# ARDEC-controller-v1.net
KiCad netlist of a schematic drawn in EAGLE
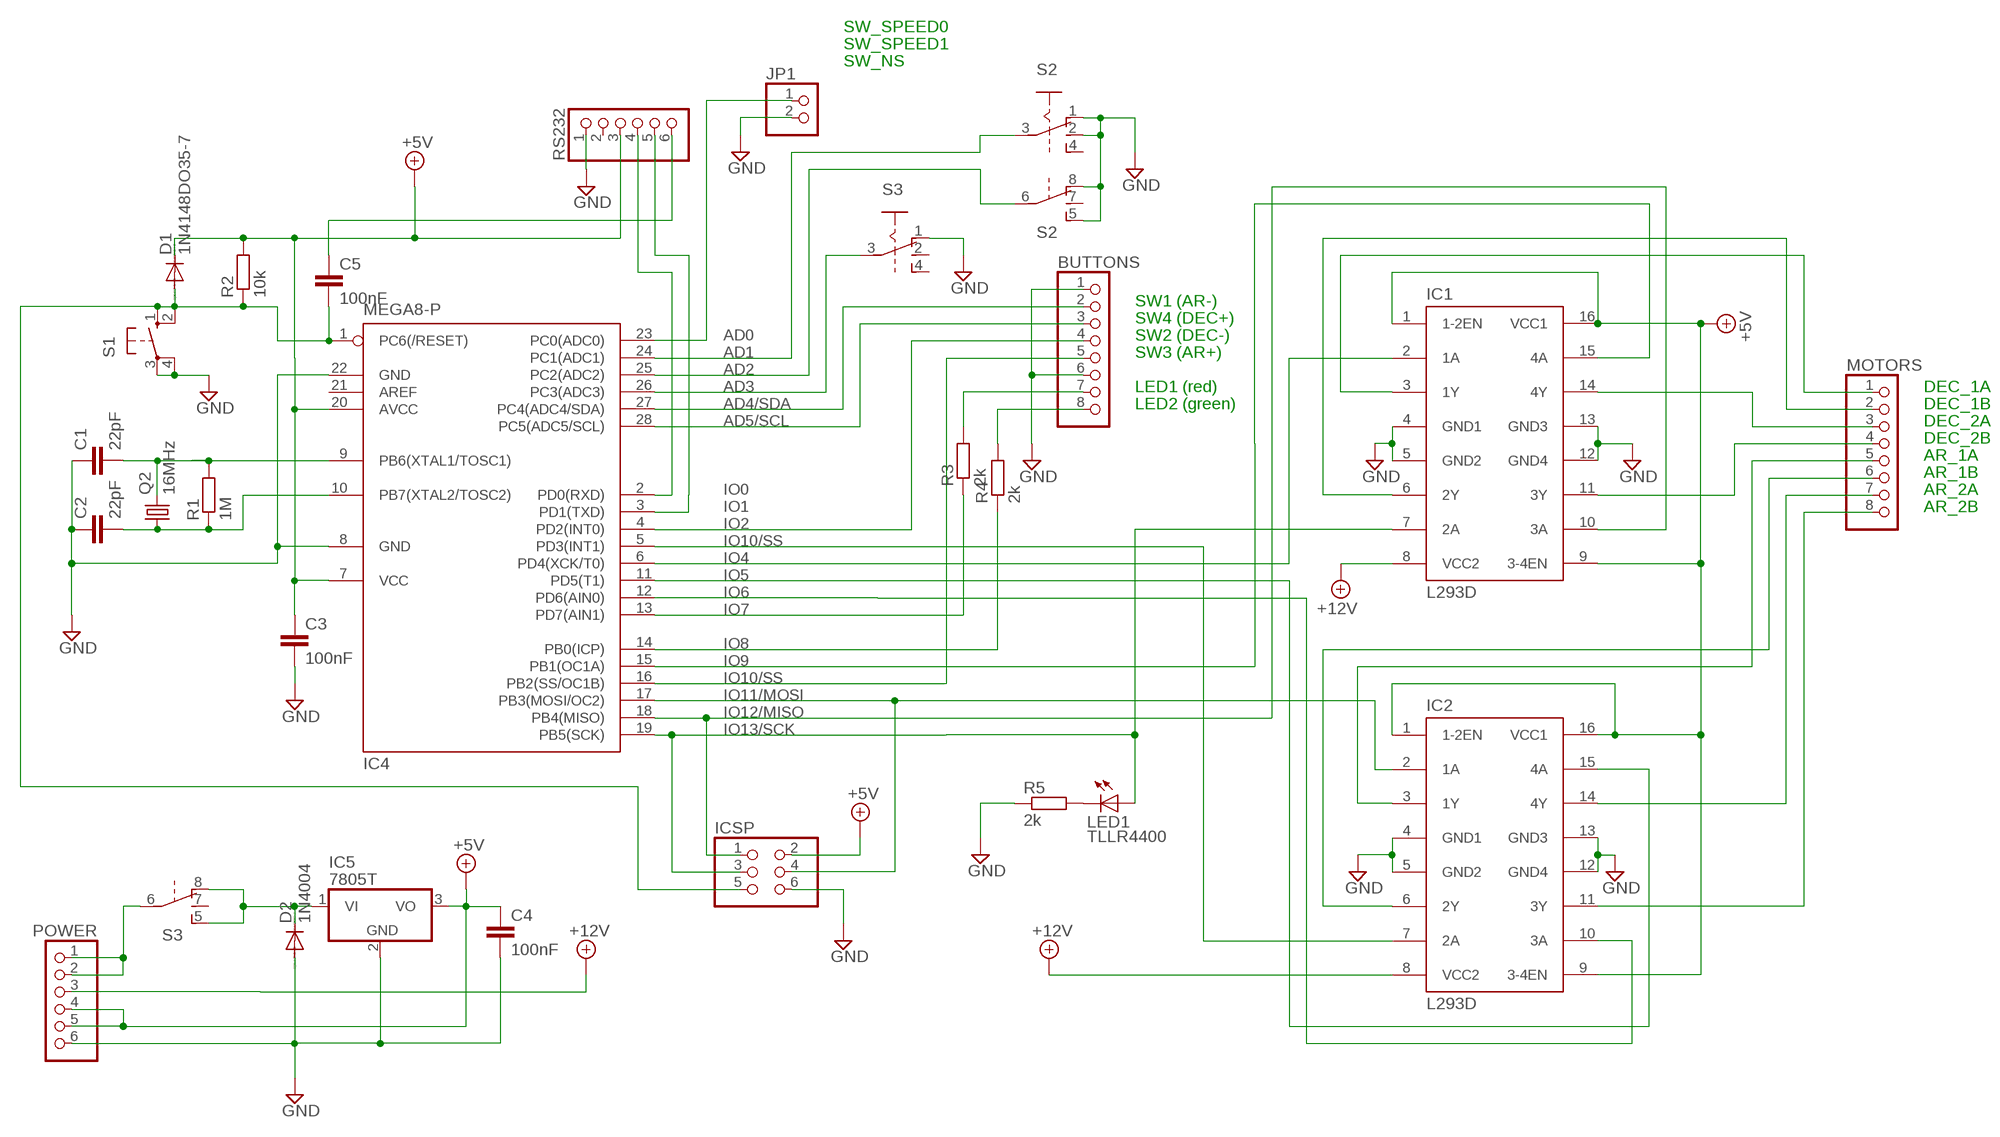
[diagram p0: schematic, sheet 1]

(export (version "E")
  (design (tool "Eeschema 10.0.6"))
  (components
    (comp (ref "BUTTONS")
      (value "PINHD-1X8")
      (footprint "eagle-import:1X08")
      (libsource (lib "eagle-import") (part "PINHD-1X8"))
    )
    (comp (ref "C1")
      (value "22pF")
      (footprint "eagle-import:C2.5-2")
      (libsource (lib "eagle-import") (part "C2.5/2"))
    )
    (comp (ref "C2")
      (value "22pF")
      (footprint "eagle-import:C2.5-2")
      (libsource (lib "eagle-import") (part "C2.5/2"))
    )
    (comp (ref "C3")
      (value "100nF")
      (footprint "eagle-import:C025_050-025X075")
      (libsource (lib "eagle-import") (part "C-EU025_050-025X075"))
    )
    (comp (ref "C4")
      (value "100nF")
      (footprint "eagle-import:C025_050-025X075")
      (libsource (lib "eagle-import") (part "C-EU025_050-025X075"))
    )
    (comp (ref "C5")
      (value "100nF")
      (footprint "eagle-import:C025_050-025X075")
      (libsource (lib "eagle-import") (part "C-EU025_050-025X075"))
    )
    (comp (ref "D1")
      (value "1N4148DO35-7")
      (footprint "eagle-import:DO35-7")
      (libsource (lib "eagle-import") (part "1N4148DO35-7"))
    )
    (comp (ref "D2")
      (value "1N4004")
      (footprint "eagle-import:DO41-10")
      (libsource (lib "eagle-import") (part "1N4004"))
    )
    (comp (ref "IC1")
      (value "L293D")
      (footprint "eagle-import:DIL16")
      (libsource (lib "eagle-import") (part "L293D"))
    )
    (comp (ref "IC2")
      (value "L293D")
      (footprint "eagle-import:DIL16")
      (libsource (lib "eagle-import") (part "L293D"))
    )
    (comp (ref "IC4")
      (value "MEGA8-P")
      (footprint "eagle-import:DIL28-3")
      (libsource (lib "eagle-import") (part "MEGA8-P"))
    )
    (comp (ref "IC5")
      (value "7805T")
      (footprint "eagle-import:TO220H")
      (libsource (lib "eagle-import") (part "78T05"))
    )
    (comp (ref "ICSP")
      (value "PINHD-2X3")
      (footprint "eagle-import:2X03")
      (libsource (lib "eagle-import") (part "PINHD-2X3"))
    )
    (comp (ref "JP1")
      (value "PINHD-1X2")
      (footprint "eagle-import:1X02")
      (libsource (lib "eagle-import") (part "PINHD-1X2"))
    )
    (comp (ref "LED1")
      (value "TLLR4400")
      (footprint "eagle-import:LED3MM")
      (fields (field (name "MF") "VISHAY SEMICONDUCTOR"))
      (libsource (lib "eagle-import") (part "TLLR4400"))
    )
    (comp (ref "MOTORS")
      (value "PINHD-1X8")
      (footprint "eagle-import:1X08")
      (libsource (lib "eagle-import") (part "PINHD-1X8"))
    )
    (comp (ref "POWER")
      (value "PINHD-1X6")
      (footprint "eagle-import:1X06")
      (libsource (lib "eagle-import") (part "PINHD-1X6"))
    )
    (comp (ref "Q2")
      (value "16MHz")
      (footprint "eagle-import:HC18U-H")
      (libsource (lib "eagle-import") (part "CRYSTALHC18U-H"))
    )
    (comp (ref "R1")
      (value "1M")
      (footprint "eagle-import:0207_10")
      (libsource (lib "eagle-import") (part "R-EU_0207/10"))
    )
    (comp (ref "R2")
      (value "10k")
      (footprint "eagle-import:0207_10")
      (libsource (lib "eagle-import") (part "R-EU_0207/10"))
    )
    (comp (ref "R3")
      (value "2k")
      (footprint "eagle-import:0207_10")
      (libsource (lib "eagle-import") (part "R-EU_0207/10"))
    )
    (comp (ref "R4")
      (value "2k")
      (footprint "eagle-import:0207_10")
      (libsource (lib "eagle-import") (part "R-EU_0207/10"))
    )
    (comp (ref "R5")
      (value "2k")
      (footprint "eagle-import:0207_10")
      (libsource (lib "eagle-import") (part "R-EU_0207/10"))
    )
    (comp (ref "RS232")
      (value "PINHD-1X6")
      (footprint "eagle-import:1X06")
      (libsource (lib "eagle-import") (part "PINHD-1X6"))
    )
    (comp (ref "S1")
      (value "10-XX")
      (footprint "eagle-import:B3F-10XX")
      (fields (field (name "MPN") "B3F-1000"))
      (libsource (lib "eagle-import") (part "10-XX"))
    )
    (comp (ref "S2")
      (value "SL2C3P")
      (footprint "eagle-import:SL2C3P")
      (libsource (lib "eagle-import") (part "SL2C3P"))
    )
    (comp (ref "S3")
      (value "SL2C3P")
      (footprint "eagle-import:SL2C3P")
      (libsource (lib "eagle-import") (part "SL2C3P"))
    )
  )
  (nets
    (net (code "1") (name "+5V") (class "Default")
      (node (ref "C3") (pin "1") (pinfunction "1_1") (pintype "passive"))
      (node (ref "C4") (pin "1") (pinfunction "1_1") (pintype "passive"))
      (node (ref "D1") (pin "C") (pinfunction "C_C") (pintype "passive"))
      (node (ref "IC1") (pin "1") (pinfunction "1-2EN_1") (pintype "input"))
      (node (ref "IC1") (pin "16") (pinfunction "VCC1_16") (pintype "power_in"))
      (node (ref "IC1") (pin "9") (pinfunction "3-4EN_9") (pintype "input"))
      (node (ref "IC2") (pin "1") (pinfunction "1-2EN_1") (pintype "input"))
      (node (ref "IC2") (pin "16") (pinfunction "VCC1_16") (pintype "power_in"))
      (node (ref "IC2") (pin "9") (pinfunction "3-4EN_9") (pintype "input"))
      (node (ref "IC4") (pin "20") (pinfunction "AVCC_20") (pintype "power_in"))
      (node (ref "IC4") (pin "7") (pinfunction "VCC_7") (pintype "power_in"))
      (node (ref "IC5") (pin "3") (pinfunction "VO_3") (pintype "passive"))
      (node (ref "ICSP") (pin "2") (pinfunction "2_2") (pintype "passive"))
      (node (ref "POWER") (pin "4") (pinfunction "4_4") (pintype "passive"))
      (node (ref "POWER") (pin "5") (pinfunction "5_5") (pintype "passive"))
      (node (ref "R2") (pin "2") (pinfunction "2_2") (pintype "passive"))
      (node (ref "RS232") (pin "3") (pinfunction "3_3") (pintype "passive"))
    )
    (net (code "2") (name "+12V") (class "Default")
      (node (ref "IC1") (pin "8") (pinfunction "VCC2_8") (pintype "power_in"))
      (node (ref "IC2") (pin "8") (pinfunction "VCC2_8") (pintype "power_in"))
      (node (ref "POWER") (pin "3") (pinfunction "3_3") (pintype "passive"))
    )
    (net (code "3") (name "/AD0") (class "Default")
      (node (ref "IC4") (pin "23") (pinfunction "PC0(ADC0)_23") (pintype "bidirectional"))
      (node (ref "JP1") (pin "1") (pinfunction "1_1") (pintype "passive"))
    )
    (net (code "4") (name "/AD1") (class "Default")
      (node (ref "IC4") (pin "24") (pinfunction "PC1(ADC1)_24") (pintype "bidirectional"))
      (node (ref "S2") (pin "3") (pinfunction "Q_3") (pintype "passive"))
    )
    (net (code "5") (name "/AD2") (class "Default")
      (node (ref "IC4") (pin "25") (pinfunction "PC2(ADC2)_25") (pintype "bidirectional"))
      (node (ref "S2") (pin "6") (pinfunction "Q_6") (pintype "passive"))
    )
    (net (code "6") (name "/AD3") (class "Default")
      (node (ref "IC4") (pin "26") (pinfunction "PC3(ADC3)_26") (pintype "bidirectional"))
      (node (ref "S3") (pin "3") (pinfunction "Q_3") (pintype "passive"))
    )
    (net (code "7") (name "/AD4{slash}SDA") (class "Default")
      (node (ref "BUTTONS") (pin "2") (pinfunction "2_2") (pintype "passive"))
      (node (ref "IC4") (pin "27") (pinfunction "PC4(ADC4/SDA)_27") (pintype "bidirectional"))
    )
    (net (code "8") (name "/AD5{slash}SCL") (class "Default")
      (node (ref "BUTTONS") (pin "3") (pinfunction "3_3") (pintype "passive"))
      (node (ref "IC4") (pin "28") (pinfunction "PC5(ADC5/SCL)_28") (pintype "bidirectional"))
    )
    (net (code "9") (name "/IO0") (class "Default")
      (node (ref "IC4") (pin "2") (pinfunction "PD0(RXD)_2") (pintype "bidirectional"))
      (node (ref "RS232") (pin "4") (pinfunction "4_4") (pintype "passive"))
    )
    (net (code "10") (name "/IO1") (class "Default")
      (node (ref "IC4") (pin "3") (pinfunction "PD1(TXD)_3") (pintype "bidirectional"))
      (node (ref "RS232") (pin "5") (pinfunction "5_5") (pintype "passive"))
    )
    (net (code "11") (name "/IO2") (class "Default")
      (node (ref "BUTTONS") (pin "4") (pinfunction "4_4") (pintype "passive"))
      (node (ref "IC4") (pin "4") (pinfunction "PD2(INT0)_4") (pintype "bidirectional"))
    )
    (net (code "12") (name "/IO4") (class "Default")
      (node (ref "IC1") (pin "2") (pinfunction "1A_2") (pintype "input"))
      (node (ref "IC4") (pin "6") (pinfunction "PD4(XCK/T0)_6") (pintype "bidirectional"))
    )
    (net (code "13") (name "/IO5") (class "Default")
      (node (ref "IC2") (pin "15") (pinfunction "4A_15") (pintype "input"))
      (node (ref "IC4") (pin "11") (pinfunction "PD5(T1)_11") (pintype "bidirectional"))
    )
    (net (code "14") (name "/IO6") (class "Default")
      (node (ref "IC2") (pin "10") (pinfunction "3A_10") (pintype "input"))
      (node (ref "IC4") (pin "12") (pinfunction "PD6(AIN0)_12") (pintype "bidirectional"))
    )
    (net (code "15") (name "/IO7") (class "Default")
      (node (ref "IC4") (pin "13") (pinfunction "PD7(AIN1)_13") (pintype "bidirectional"))
      (node (ref "R3") (pin "1") (pinfunction "1_1") (pintype "passive"))
    )
    (net (code "16") (name "/IO8") (class "Default")
      (node (ref "IC4") (pin "14") (pinfunction "PB0(ICP)_14") (pintype "bidirectional"))
      (node (ref "R4") (pin "1") (pinfunction "1_1") (pintype "passive"))
    )
    (net (code "17") (name "/IO9") (class "Default")
      (node (ref "IC1") (pin "15") (pinfunction "4A_15") (pintype "input"))
      (node (ref "IC4") (pin "15") (pinfunction "PB1(OC1A)_15") (pintype "bidirectional"))
    )
    (net (code "18") (name "/IO10{slash}SS") (class "Default")
      (node (ref "BUTTONS") (pin "5") (pinfunction "5_5") (pintype "passive"))
      (node (ref "IC4") (pin "16") (pinfunction "PB2(SS/OC1B)_16") (pintype "bidirectional"))
    )
    (net (code "19") (name "/IO11{slash}MOSI") (class "Default")
      (node (ref "IC2") (pin "2") (pinfunction "1A_2") (pintype "input"))
      (node (ref "IC4") (pin "17") (pinfunction "PB3(MOSI/OC2)_17") (pintype "bidirectional"))
      (node (ref "ICSP") (pin "4") (pinfunction "4_4") (pintype "passive"))
    )
    (net (code "20") (name "/IO12{slash}MISO") (class "Default")
      (node (ref "IC1") (pin "10") (pinfunction "3A_10") (pintype "input"))
      (node (ref "IC4") (pin "18") (pinfunction "PB4(MISO)_18") (pintype "bidirectional"))
      (node (ref "ICSP") (pin "1") (pinfunction "1_1") (pintype "passive"))
    )
    (net (code "21") (name "/IO13{slash}SCK") (class "Default")
      (node (ref "IC1") (pin "7") (pinfunction "2A_7") (pintype "input"))
      (node (ref "IC4") (pin "19") (pinfunction "PB5(SCK)_19") (pintype "bidirectional"))
      (node (ref "ICSP") (pin "3") (pinfunction "3_3") (pintype "passive"))
      (node (ref "LED1") (pin "A") (pinfunction "A_A") (pintype "passive"))
    )
    (net (code "22") (name "GND") (class "Default")
      (node (ref "BUTTONS") (pin "1") (pinfunction "1_1") (pintype "passive"))
      (node (ref "BUTTONS") (pin "6") (pinfunction "6_6") (pintype "passive"))
      (node (ref "C1") (pin "1") (pinfunction "1_1") (pintype "passive"))
      (node (ref "C2") (pin "1") (pinfunction "1_1") (pintype "passive"))
      (node (ref "C3") (pin "2") (pinfunction "2_2") (pintype "passive"))
      (node (ref "C4") (pin "2") (pinfunction "2_2") (pintype "passive"))
      (node (ref "D2") (pin "A") (pinfunction "A_A") (pintype "passive"))
      (node (ref "IC1") (pin "12") (pinfunction "GND4_12") (pintype "power_in"))
      (node (ref "IC1") (pin "13") (pinfunction "GND3_13") (pintype "power_in"))
      (node (ref "IC1") (pin "4") (pinfunction "GND1_4") (pintype "power_in"))
      (node (ref "IC1") (pin "5") (pinfunction "GND2_5") (pintype "power_in"))
      (node (ref "IC2") (pin "12") (pinfunction "GND4_12") (pintype "power_in"))
      (node (ref "IC2") (pin "13") (pinfunction "GND3_13") (pintype "power_in"))
      (node (ref "IC2") (pin "4") (pinfunction "GND1_4") (pintype "power_in"))
      (node (ref "IC2") (pin "5") (pinfunction "GND2_5") (pintype "power_in"))
      (node (ref "IC4") (pin "22") (pinfunction "GND_22") (pintype "power_in"))
      (node (ref "IC4") (pin "8") (pinfunction "GND_8") (pintype "power_in"))
      (node (ref "IC5") (pin "2") (pinfunction "GND_2") (pintype "passive"))
      (node (ref "ICSP") (pin "6") (pinfunction "6_6") (pintype "passive"))
      (node (ref "JP1") (pin "2") (pinfunction "2_2") (pintype "passive"))
      (node (ref "POWER") (pin "6") (pinfunction "6_6") (pintype "passive"))
      (node (ref "R5") (pin "1") (pinfunction "1_1") (pintype "passive"))
      (node (ref "RS232") (pin "1") (pinfunction "1_1") (pintype "passive"))
      (node (ref "S1") (pin "3") (pinfunction "P_3") (pintype "passive"))
      (node (ref "S1") (pin "4") (pinfunction "P1_4") (pintype "passive"))
      (node (ref "S2") (pin "1") (pinfunction "O_1") (pintype "passive"))
      (node (ref "S2") (pin "2") (pinfunction "P_2") (pintype "passive"))
      (node (ref "S2") (pin "5") (pinfunction "R_5") (pintype "passive"))
      (node (ref "S2") (pin "8") (pinfunction "O_8") (pintype "passive"))
      (node (ref "S3") (pin "1") (pinfunction "O_1") (pintype "passive"))
    )
    (net (code "23") (name "Net-(BUTTONS-Pad7)") (class "Default")
      (node (ref "BUTTONS") (pin "7") (pinfunction "7_7") (pintype "passive"))
      (node (ref "R3") (pin "2") (pinfunction "2_2") (pintype "passive"))
    )
    (net (code "24") (name "Net-(BUTTONS-Pad8)") (class "Default")
      (node (ref "BUTTONS") (pin "8") (pinfunction "8_8") (pintype "passive"))
      (node (ref "R4") (pin "2") (pinfunction "2_2") (pintype "passive"))
    )
    (net (code "25") (name "Net-(C5-Pad1)") (class "Default")
      (node (ref "C5") (pin "1") (pinfunction "1_1") (pintype "passive"))
      (node (ref "RS232") (pin "6") (pinfunction "6_6") (pintype "passive"))
    )
    (net (code "26") (name "Net-(IC1-1Y)") (class "Default")
      (node (ref "IC1") (pin "3") (pinfunction "1Y_3") (pintype "output"))
      (node (ref "MOTORS") (pin "1") (pinfunction "1_1") (pintype "passive"))
    )
    (net (code "27") (name "Net-(IC1-2Y)") (class "Default")
      (node (ref "IC1") (pin "6") (pinfunction "2Y_6") (pintype "output"))
      (node (ref "MOTORS") (pin "2") (pinfunction "2_2") (pintype "passive"))
    )
    (net (code "28") (name "Net-(IC1-3Y)") (class "Default")
      (node (ref "IC1") (pin "11") (pinfunction "3Y_11") (pintype "output"))
      (node (ref "MOTORS") (pin "4") (pinfunction "4_4") (pintype "passive"))
    )
    (net (code "29") (name "Net-(IC1-4Y)") (class "Default")
      (node (ref "IC1") (pin "14") (pinfunction "4Y_14") (pintype "output"))
      (node (ref "MOTORS") (pin "3") (pinfunction "3_3") (pintype "passive"))
    )
    (net (code "30") (name "Net-(IC2-1Y)") (class "Default")
      (node (ref "IC2") (pin "3") (pinfunction "1Y_3") (pintype "output"))
      (node (ref "MOTORS") (pin "5") (pinfunction "5_5") (pintype "passive"))
    )
    (net (code "31") (name "Net-(IC2-2A)") (class "Default")
      (node (ref "IC2") (pin "7") (pinfunction "2A_7") (pintype "input"))
      (node (ref "IC4") (pin "5") (pinfunction "PD3(INT1)_5") (pintype "bidirectional"))
    )
    (net (code "32") (name "Net-(IC2-2Y)") (class "Default")
      (node (ref "IC2") (pin "6") (pinfunction "2Y_6") (pintype "output"))
      (node (ref "MOTORS") (pin "6") (pinfunction "6_6") (pintype "passive"))
    )
    (net (code "33") (name "Net-(IC2-3Y)") (class "Default")
      (node (ref "IC2") (pin "11") (pinfunction "3Y_11") (pintype "output"))
      (node (ref "MOTORS") (pin "8") (pinfunction "8_8") (pintype "passive"))
    )
    (net (code "34") (name "Net-(IC2-4Y)") (class "Default")
      (node (ref "IC2") (pin "14") (pinfunction "4Y_14") (pintype "output"))
      (node (ref "MOTORS") (pin "7") (pinfunction "7_7") (pintype "passive"))
    )
    (net (code "35") (name "Net-(IC4-PB6(XTAL1{slash}TOSC1))") (class "Default")
      (node (ref "C1") (pin "2") (pinfunction "2_2") (pintype "passive"))
      (node (ref "IC4") (pin "9") (pinfunction "PB6(XTAL1/TOSC1)_9") (pintype "bidirectional"))
      (node (ref "Q2") (pin "2") (pinfunction "2_2") (pintype "passive"))
      (node (ref "R1") (pin "2") (pinfunction "2_2") (pintype "passive"))
    )
    (net (code "36") (name "Net-(IC4-PB7(XTAL2{slash}TOSC2))") (class "Default")
      (node (ref "C2") (pin "2") (pinfunction "2_2") (pintype "passive"))
      (node (ref "IC4") (pin "10") (pinfunction "PB7(XTAL2/TOSC2)_10") (pintype "bidirectional"))
      (node (ref "Q2") (pin "1") (pinfunction "1_1") (pintype "passive"))
      (node (ref "R1") (pin "1") (pinfunction "1_1") (pintype "passive"))
    )
    (net (code "37") (name "Net-(IC4-PC6({slash}RESET))") (class "Default")
      (node (ref "C5") (pin "2") (pinfunction "2_2") (pintype "passive"))
      (node (ref "D1") (pin "A") (pinfunction "A_A") (pintype "passive"))
      (node (ref "IC4") (pin "1") (pinfunction "PC6(/RESET)_1") (pintype "bidirectional"))
      (node (ref "ICSP") (pin "5") (pinfunction "5_5") (pintype "passive"))
      (node (ref "R2") (pin "1") (pinfunction "1_1") (pintype "passive"))
      (node (ref "S1") (pin "1") (pinfunction "S_1") (pintype "passive"))
      (node (ref "S1") (pin "2") (pinfunction "S1_2") (pintype "passive"))
    )
    (net (code "38") (name "Net-(IC5-VI)") (class "Default")
      (node (ref "D2") (pin "C") (pinfunction "C_C") (pintype "passive"))
      (node (ref "IC5") (pin "1") (pinfunction "VI_1") (pintype "input"))
      (node (ref "S3") (pin "5") (pinfunction "R_5") (pintype "passive"))
      (node (ref "S3") (pin "8") (pinfunction "O_8") (pintype "passive"))
    )
    (net (code "39") (name "Net-(LED1-C)") (class "Default")
      (node (ref "LED1") (pin "K") (pinfunction "C_K") (pintype "passive"))
      (node (ref "R5") (pin "2") (pinfunction "2_2") (pintype "passive"))
    )
    (net (code "40") (name "Net-(S3B-Q)") (class "Default")
      (node (ref "POWER") (pin "1") (pinfunction "1_1") (pintype "passive"))
      (node (ref "POWER") (pin "2") (pinfunction "2_2") (pintype "passive"))
      (node (ref "S3") (pin "6") (pinfunction "Q_6") (pintype "passive"))
    )
    (net (code "41") (name "unconnected-(IC4-AREF-Pad21)") (class "Default")
      (node (ref "IC4") (pin "21") (pinfunction "AREF_21") (pintype "passive"))
    )
    (net (code "42") (name "unconnected-(RS232-Pad2)") (class "Default")
      (node (ref "RS232") (pin "2") (pinfunction "2_2") (pintype "passive"))
    )
    (net (code "43") (name "unconnected-(S2A-R-Pad4)") (class "Default")
      (node (ref "S2") (pin "4") (pinfunction "R_4") (pintype "passive"))
    )
    (net (code "44") (name "unconnected-(S2B-P-Pad7)") (class "Default")
      (node (ref "S2") (pin "7") (pinfunction "P_7") (pintype "passive"))
    )
    (net (code "45") (name "unconnected-(S3A-P-Pad2)") (class "Default")
      (node (ref "S3") (pin "2") (pinfunction "P_2") (pintype "passive"))
    )
    (net (code "46") (name "unconnected-(S3A-R-Pad4)") (class "Default")
      (node (ref "S3") (pin "4") (pinfunction "R_4") (pintype "passive"))
    )
    (net (code "47") (name "unconnected-(S3B-P-Pad7)") (class "Default")
      (node (ref "S3") (pin "7") (pinfunction "P_7") (pintype "passive"))
    )
  )
)
